# TOP_SHEET.net
KiCad netlist of a schematic drawn in Altium Designer
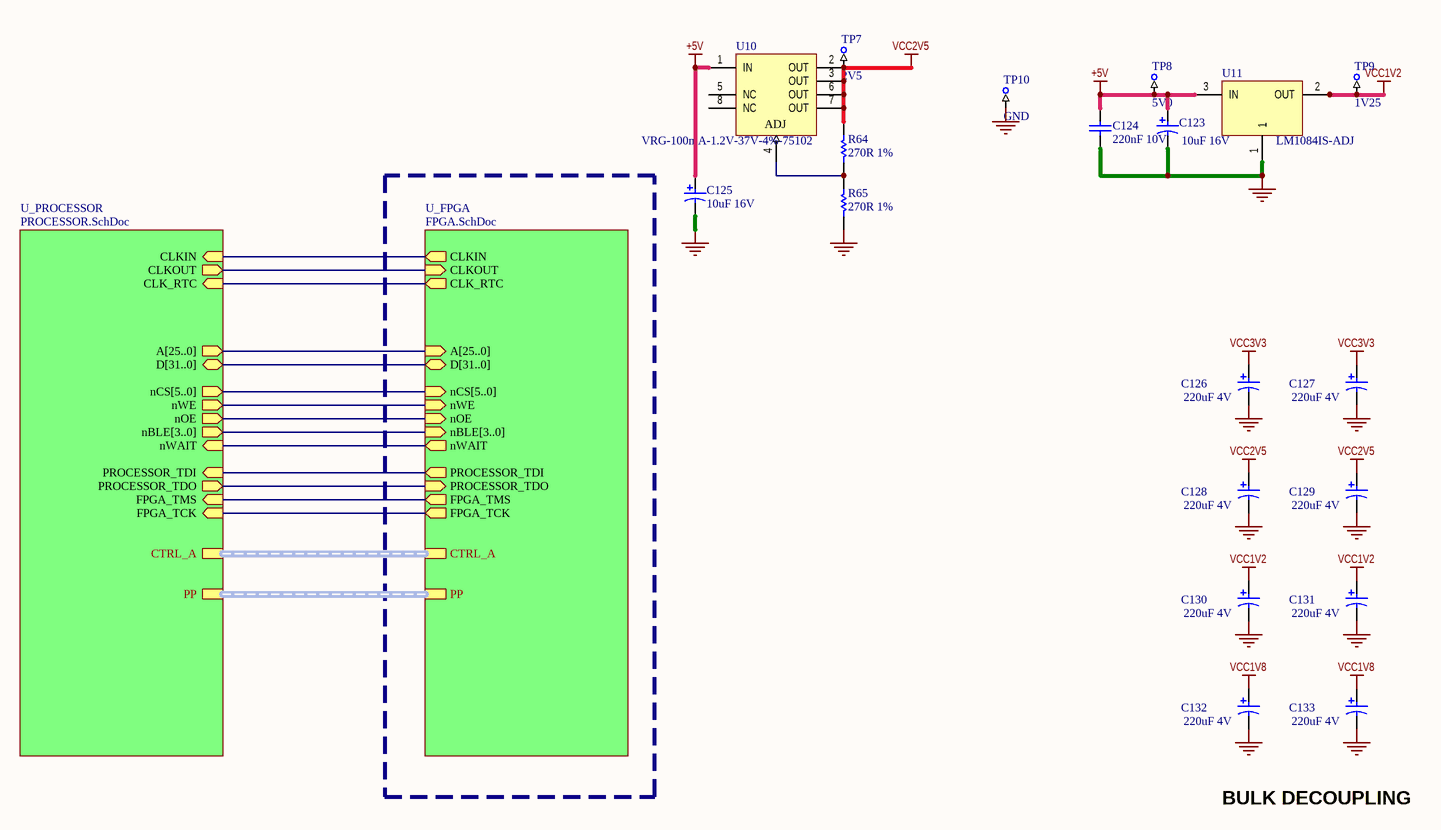
[diagram p0: TOP_SHEET.SchDoc]

(export (version "E")
  (design (tool "Eeschema 10.0.6"))
  (components
    (comp (ref "C123")
      (value "10uF 16V")
      (footprint "CAPC3528")
      (description "Polar Capacitor")
      (libsource (lib "Altium Design Library") (part "CAP-P"))
    )
    (comp (ref "C124")
      (value "220nF 10V")
      (footprint "CAPC1608")
      (description "Capacitor")
      (libsource (lib "Altium Design Library") (part "CAP-NP"))
    )
    (comp (ref "C125")
      (value "10uF 16V")
      (footprint "CAPC3528")
      (description "Polar Capacitor")
      (libsource (lib "Altium Design Library") (part "CAP-P"))
    )
    (comp (ref "C126")
      (value "220uF 4V")
      (footprint "CAPC7343")
      (description "Polar Capacitor")
      (libsource (lib "Altium Design Library") (part "CAP-P"))
    )
    (comp (ref "C127")
      (value "220uF 4V")
      (footprint "CAPC7343")
      (description "Polar Capacitor")
      (libsource (lib "Altium Design Library") (part "CAP-P"))
    )
    (comp (ref "C128")
      (value "220uF 4V")
      (footprint "CAPC7343")
      (description "Polar Capacitor")
      (libsource (lib "Altium Design Library") (part "CAP-P"))
    )
    (comp (ref "C129")
      (value "220uF 4V")
      (footprint "CAPC7343")
      (description "Polar Capacitor")
      (libsource (lib "Altium Design Library") (part "CAP-P"))
    )
    (comp (ref "C130")
      (value "220uF 4V")
      (footprint "CAPC7343")
      (description "Polar Capacitor")
      (libsource (lib "Altium Design Library") (part "CAP-P"))
    )
    (comp (ref "C131")
      (value "220uF 4V")
      (footprint "CAPC7343")
      (description "Polar Capacitor")
      (libsource (lib "Altium Design Library") (part "CAP-P"))
    )
    (comp (ref "C132")
      (value "220uF 4V")
      (footprint "CAPC7343")
      (description "Polar Capacitor")
      (libsource (lib "Altium Design Library") (part "CAP-P"))
    )
    (comp (ref "C133")
      (value "220uF 4V")
      (footprint "CAPC7343")
      (description "Polar Capacitor")
      (libsource (lib "Altium Design Library") (part "CAP-P"))
    )
    (comp (ref "R64")
      (value "270R 1%")
      (footprint "RESC2012")
      (description "Resistor")
      (libsource (lib "Altium Design Library") (part "RES"))
    )
    (comp (ref "R65")
      (value "270R 1%")
      (footprint "RESC2012")
      (description "Resistor")
      (libsource (lib "Altium Design Library") (part "RES"))
    )
    (comp (ref "TP7")
      (value "2V5")
      (footprint "TestPin")
      (libsource (lib "Altium Design Library") (part "TestPin"))
    )
    (comp (ref "TP8")
      (value "5V0")
      (footprint "TestPin")
      (libsource (lib "Altium Design Library") (part "TestPin"))
    )
    (comp (ref "TP9")
      (value "1V25")
      (footprint "TestPin")
      (libsource (lib "Altium Design Library") (part "TestPin"))
    )
    (comp (ref "TP10")
      (value "GND")
      (footprint "TestPin")
      (libsource (lib "Altium Design Library") (part "TestPin"))
    )
    (comp (ref "U10")
      (value "VRG-100mA-1.2V-37V-4%-75102")
      (footprint "SOP127P600-8")
      (description "Low Current 3-Terminal Adjustable Positive Voltage Regulator")
      (libsource (lib "Altium Design Library") (part "VRG-ADJ-8"))
    )
    (comp (ref "U11")
      (value "LM1084IS-ADJ")
      (footprint "TO254P1435-4")
      (description "5A Low Dropout Positive Regulators")
      (libsource (lib "Altium Design Library") (part "VRG-ADJ-3"))
    )
  )
  (nets
    (net (code "1") (name "+5V") (class "Default")
      (node (ref "C123") (pin "1") (pinfunction "1_1") (pintype "passive"))
      (node (ref "C124") (pin "1") (pinfunction "1_1") (pintype "passive"))
      (node (ref "C125") (pin "1") (pinfunction "1_1") (pintype "passive"))
      (node (ref "TP8") (pin "1") (pinfunction "1_1") (pintype "input"))
      (node (ref "U10") (pin "1") (pinfunction "IN_1") (pintype "power_in"))
      (node (ref "U11") (pin "3") (pinfunction "IN_3") (pintype "power_in"))
    )
    (net (code "18") (name "GND") (class "Default")
      (node (ref "C123") (pin "2") (pinfunction "2_2") (pintype "passive"))
      (node (ref "C124") (pin "2") (pinfunction "2_2") (pintype "passive"))
      (node (ref "C125") (pin "2") (pinfunction "2_2") (pintype "passive"))
      (node (ref "C126") (pin "2") (pinfunction "2_2") (pintype "passive"))
      (node (ref "C127") (pin "2") (pinfunction "2_2") (pintype "passive"))
      (node (ref "C128") (pin "2") (pinfunction "2_2") (pintype "passive"))
      (node (ref "C129") (pin "2") (pinfunction "2_2") (pintype "passive"))
      (node (ref "C130") (pin "2") (pinfunction "2_2") (pintype "passive"))
      (node (ref "C131") (pin "2") (pinfunction "2_2") (pintype "passive"))
      (node (ref "C132") (pin "2") (pinfunction "2_2") (pintype "passive"))
      (node (ref "C133") (pin "2") (pinfunction "2_2") (pintype "passive"))
      (node (ref "R65") (pin "2") (pinfunction "2_2") (pintype "passive"))
      (node (ref "TP10") (pin "1") (pinfunction "1_1") (pintype "input"))
      (node (ref "U11") (pin "1") (pinfunction "1_1") (pintype "passive"))
    )
    (net (code "19") (name "Net-(U10-ADJ)") (class "Default")
      (node (ref "R64") (pin "2") (pinfunction "2_2") (pintype "passive"))
      (node (ref "R65") (pin "1") (pinfunction "1_1") (pintype "passive"))
      (node (ref "U10") (pin "4") (pinfunction "ADJ_4") (pintype "input"))
    )
    (net (code "20") (name "VCC1V2") (class "Default")
      (node (ref "C130") (pin "1") (pinfunction "1_1") (pintype "passive"))
      (node (ref "C131") (pin "1") (pinfunction "1_1") (pintype "passive"))
      (node (ref "TP9") (pin "1") (pinfunction "1_1") (pintype "input"))
      (node (ref "U11") (pin "2") (pinfunction "OUT_2") (pintype "power_in"))
      (node (ref "U11") (pin "4") (pinfunction "HeatSink_4") (pintype "power_in"))
    )
    (net (code "21") (name "VCC1V8") (class "Default")
      (node (ref "C132") (pin "1") (pinfunction "1_1") (pintype "passive"))
      (node (ref "C133") (pin "1") (pinfunction "1_1") (pintype "passive"))
    )
    (net (code "22") (name "VCC2V5") (class "Default")
      (node (ref "C128") (pin "1") (pinfunction "1_1") (pintype "passive"))
      (node (ref "C129") (pin "1") (pinfunction "1_1") (pintype "passive"))
      (node (ref "R64") (pin "1") (pinfunction "1_1") (pintype "passive"))
      (node (ref "TP7") (pin "1") (pinfunction "1_1") (pintype "input"))
      (node (ref "U10") (pin "2") (pinfunction "OUT_2") (pintype "power_in"))
      (node (ref "U10") (pin "3") (pinfunction "OUT_3") (pintype "power_in"))
      (node (ref "U10") (pin "6") (pinfunction "OUT_6") (pintype "power_in"))
      (node (ref "U10") (pin "7") (pinfunction "OUT_7") (pintype "power_in"))
    )
    (net (code "23") (name "VCC3V3") (class "Default")
      (node (ref "C126") (pin "1") (pinfunction "1_1") (pintype "passive"))
      (node (ref "C127") (pin "1") (pinfunction "1_1") (pintype "passive"))
    )
    (net (code "24") (name "unconnected-(U10-NC-Pad5)") (class "Default")
      (node (ref "U10") (pin "5") (pinfunction "NC_5") (pintype "passive"))
    )
    (net (code "25") (name "unconnected-(U10-NC-Pad8)") (class "Default")
      (node (ref "U10") (pin "8") (pinfunction "NC_8") (pintype "passive"))
    )
  )
)
